# lab_1_arhipov_usb_i2c.net
KiCad netlist of a schematic drawn in Altium Designer
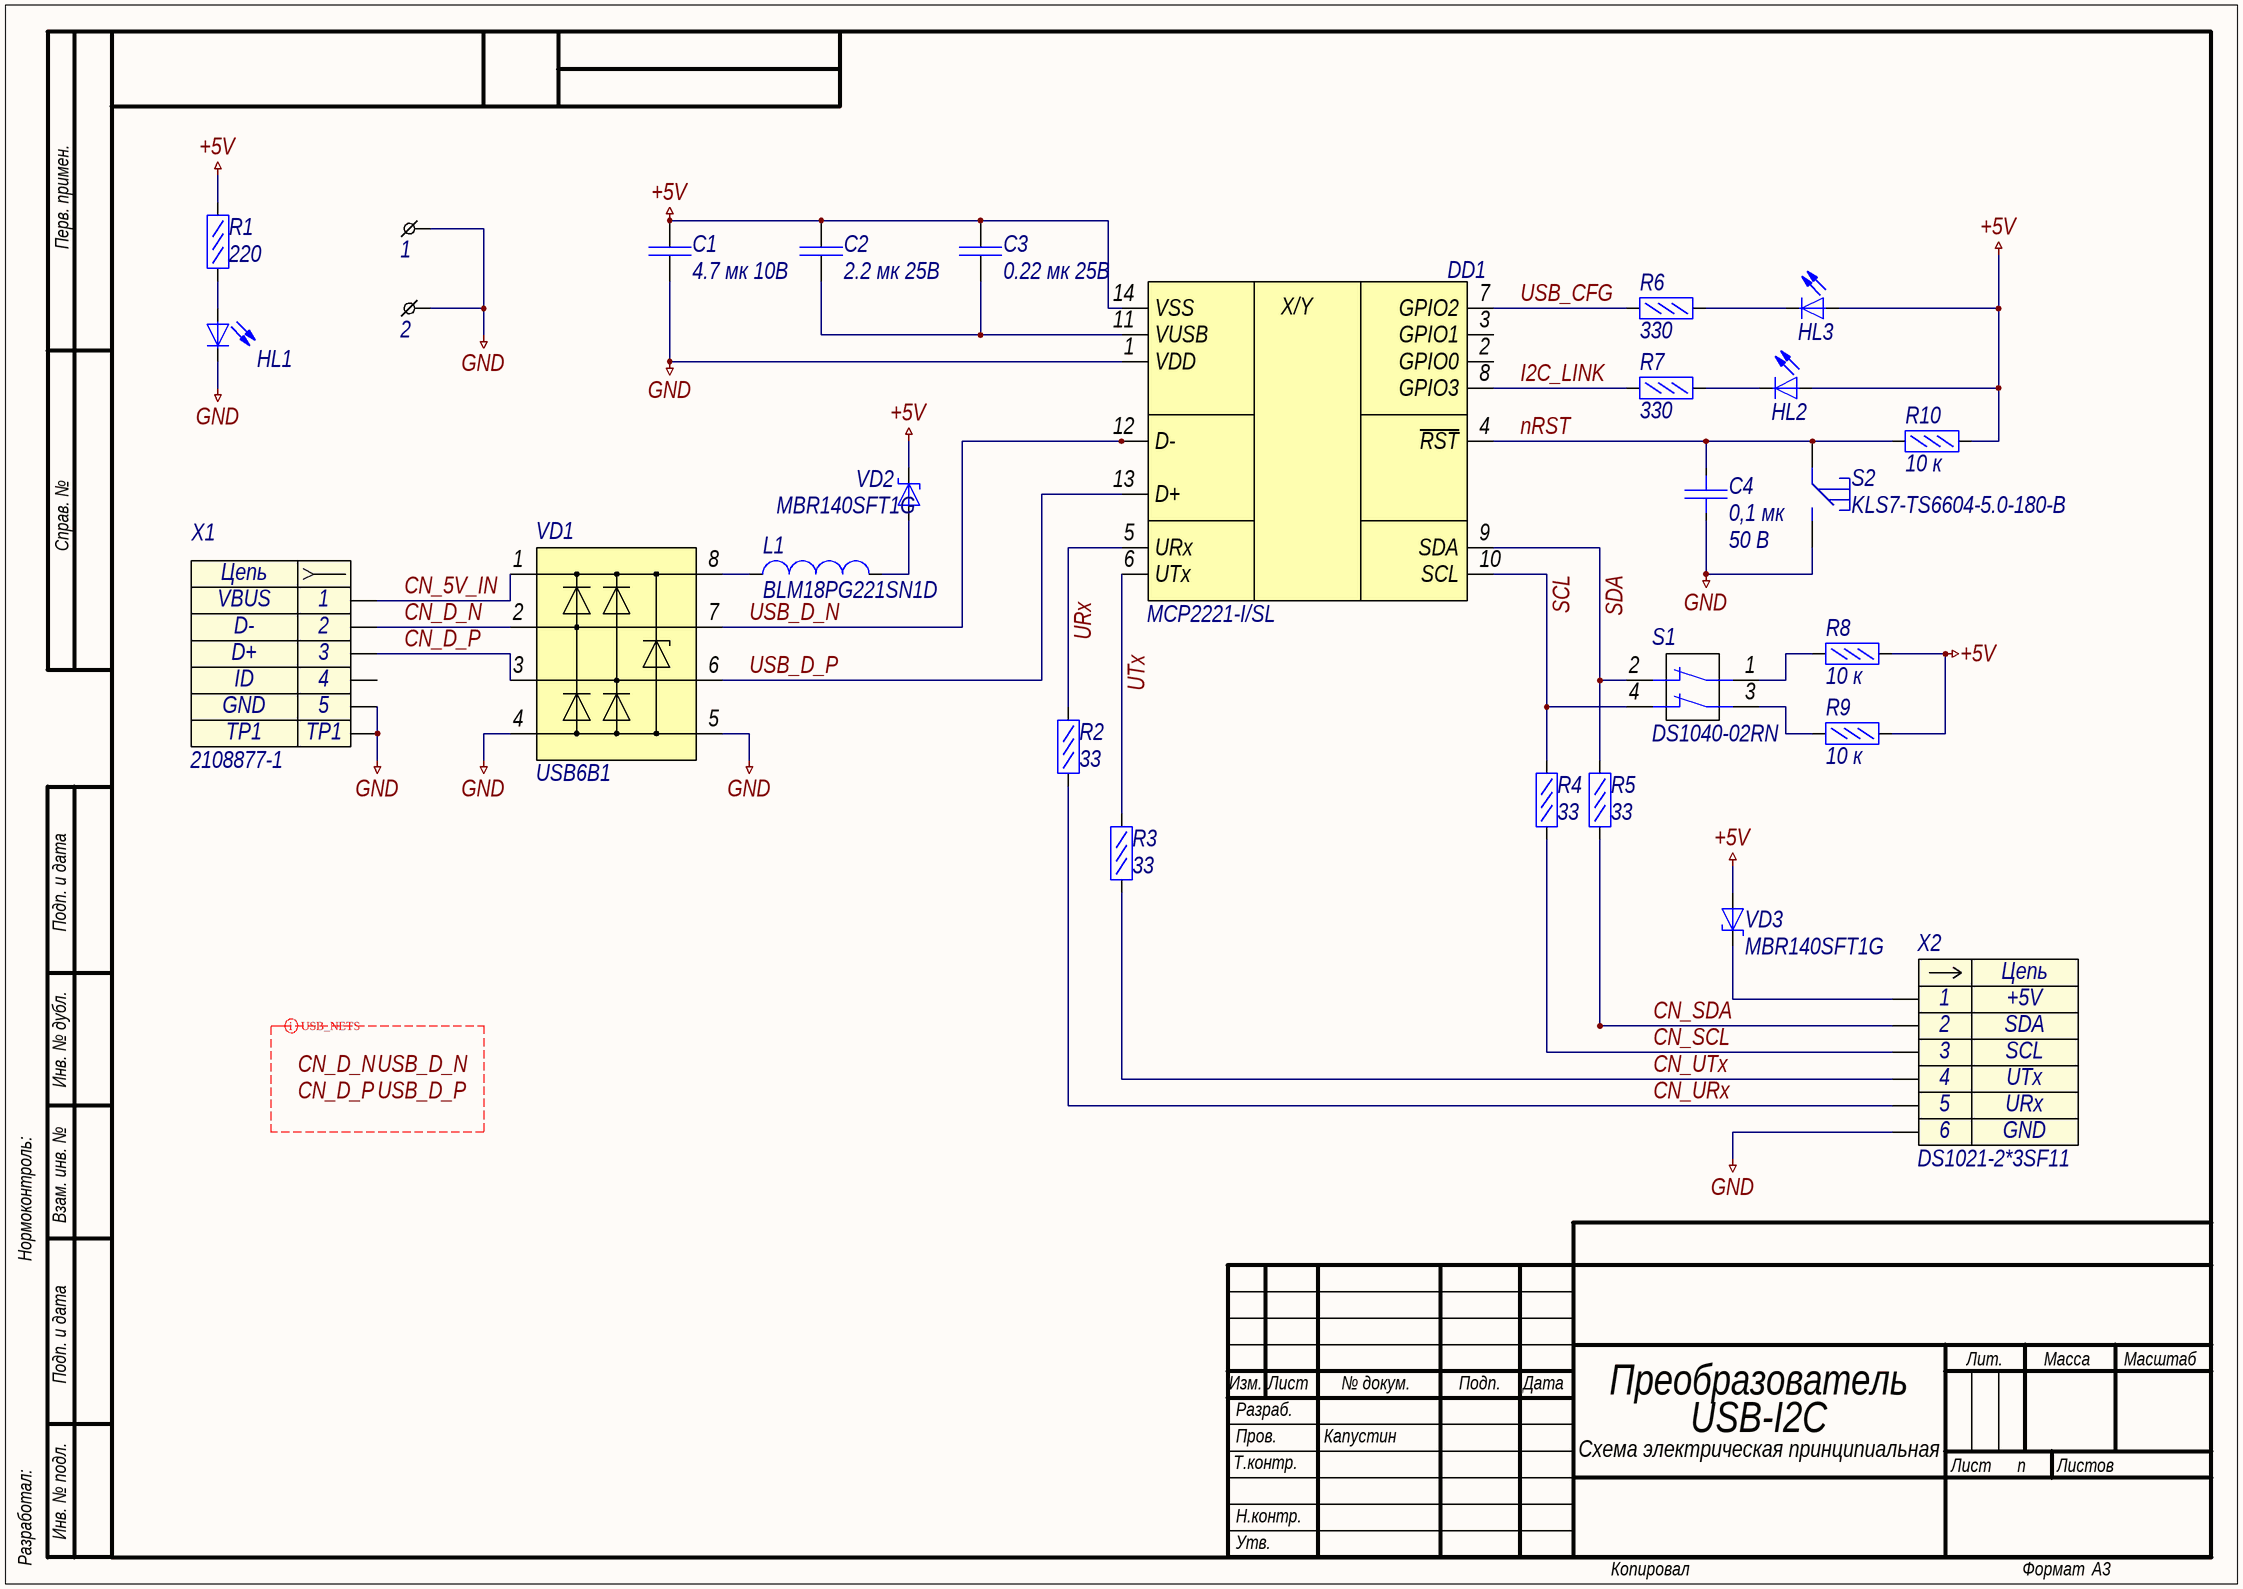
[diagram p0: lab_1_arhipov_usb_i2c.SchDoc]

(export (version "E")
  (design (tool "Eeschema 10.0.6"))
  (components
    (comp (ref "1")
      (value "MOUNTING_HOLE")
      (footprint "HOLE_1,6X3,3")
      (libsource (lib "Lib") (part "Отверстие 1,6x3,3"))
    )
    (comp (ref "2")
      (value "MOUNTING_HOLE")
      (footprint "HOLE_1,6X3,3")
      (libsource (lib "Lib") (part "Отверстие 1,6x3,3"))
    )
    (comp (ref "C1")
      (value "4.7 мк 10В")
      (footprint "c0805:C0805")
      (description "=Описание")
      (libsource (lib "Database_Students") (part "C-10.0V4.7mkF"))
    )
    (comp (ref "C2")
      (value "2.2 мк 25В")
      (footprint "c1206:C1206")
      (description "=Описание")
      (libsource (lib "Database_Students") (part "C-25.0V2.2mkF"))
    )
    (comp (ref "C3")
      (value "0.22 мк 25В")
      (footprint "smd2220")
      (description "=Описание")
      (libsource (lib "Database_Students") (part "C-25.0V0.22mkF"))
    )
    (comp (ref "C4")
      (value "0,1 мк")
      (footprint "C0603")
      (description "Конденсатор")
      (fields (field (name "НАПРЯЖЕНИЕ") "50 В"))
      (libsource (lib "Lib") (part "CL10B104KB8NNN"))
    )
    (comp (ref "DD1")
      (value "MCP2221-I/SL")
      (footprint "mcp2221:SOIC127P600X175-14N")
      (libsource (lib "mcp2221") (part "mcp2221"))
    )
    (comp (ref "HL1") (value "KP-1608SGC") (footprint "D0603") (libsource (lib "Lib") (part "KP-1608SGC")))
    (comp (ref "HL2") (value "KP-1608SGC") (footprint "D0603") (libsource (lib "Lib") (part "KP-1608SGC")))
    (comp (ref "HL3") (value "KP-1608SGC") (footprint "D0603") (libsource (lib "Lib") (part "KP-1608SGC")))
    (comp (ref "L1")
      (value "BLM18PG221SN1D")
      (footprint "L0603")
      (libsource (lib "Lib") (part "BLM18PG221SN1D"))
    )
    (comp (ref "R1")
      (value "220")
      (footprint "R0603")
      (description "Резистор 0,063Вт")
      (libsource (lib "Lib") (part "RC0603FR-07220RL"))
    )
    (comp (ref "R2")
      (value "33")
      (footprint "R0603")
      (description "Резистор 0,063Вт")
      (libsource (lib "Lib") (part "RC0603FR-0733RL"))
    )
    (comp (ref "R3")
      (value "33")
      (footprint "R0603")
      (description "Резистор 0,063Вт")
      (libsource (lib "Lib") (part "RC0603FR-0733RL"))
    )
    (comp (ref "R4")
      (value "33")
      (footprint "R0603")
      (description "Резистор 0,063Вт")
      (libsource (lib "Lib") (part "RC0603FR-0733RL"))
    )
    (comp (ref "R5")
      (value "33")
      (footprint "R0603")
      (description "Резистор 0,063Вт")
      (libsource (lib "Lib") (part "RC0603FR-0733RL"))
    )
    (comp (ref "R6")
      (value "330")
      (footprint "R0603")
      (description "Резистор 0,063Вт")
      (libsource (lib "Lib") (part "RC0603FR-07330RL"))
    )
    (comp (ref "R7")
      (value "330")
      (footprint "R0603")
      (description "Резистор 0,063Вт")
      (libsource (lib "Lib") (part "RC0603FR-07330RL"))
    )
    (comp (ref "R8")
      (value "10 к")
      (footprint "Lib:R0603")
      (description "Резистор 0,063Вт")
      (libsource (lib "Lib") (part "RC0603FR-0710KL"))
    )
    (comp (ref "R9")
      (value "10 к")
      (footprint "Lib:R0603")
      (description "Резистор 0,063Вт")
      (libsource (lib "Lib") (part "RC0603FR-0710KL"))
    )
    (comp (ref "R10")
      (value "10 к")
      (footprint "R0603")
      (description "Резистор 0,063Вт")
      (libsource (lib "Lib") (part "RC0603FR-0710KL"))
    )
    (comp (ref "S1")
      (value "DS1040-02RN")
      (footprint "Lib:DS1040-02RN")
      (libsource (lib "Lib") (part "DS1040-02RN_1"))
    )
    (comp (ref "S2")
      (value "KLS7-TS6604-5.0-180-B")
      (footprint "KLS7-TS6604_500")
      (libsource (lib "Lib") (part "KLS7-TS6604-5.0-180-B"))
    )
    (comp (ref "VD1") (value "USB6B1") (footprint "SO-8") (libsource (lib "Lib") (part "USB6B1")))
    (comp (ref "VD2")
      (value "MBR140SFT1G")
      (footprint "SOD-123FL_290X180X98")
      (libsource (lib "Lib") (part "MBR140SFT1G"))
    )
    (comp (ref "VD3")
      (value "MBR140SFT1G")
      (footprint "SOD-123FL_290X180X98")
      (libsource (lib "Lib") (part "MBR140SFT1G"))
    )
    (comp (ref "X1")
      (value "2108877-1")
      (footprint "2108877-1")
      (libsource (lib "2108877-1_micro_usb-b") (part "2108877-1_micro_usb-b"))
    )
    (comp (ref "X2")
      (value "DS1021-2*3SF11")
      (footprint "Lib:PLS-2,54-2X3-THT-V")
      (libsource (lib "Lib") (part "DS1021-2*3SF11"))
    )
  )
  (nets
    (net (code "1") (name "+5V") (class "Default")
      (node (ref "C1") (pin "2") (pinfunction "2_2") (pintype "passive"))
      (node (ref "C2") (pin "2") (pinfunction "2_2") (pintype "passive"))
      (node (ref "C3") (pin "2") (pinfunction "2_2") (pintype "passive"))
      (node (ref "DD1") (pin "14") (pinfunction "VSS_14") (pintype "passive"))
      (node (ref "HL2") (pin "1") (pinfunction "A_1") (pintype "passive"))
      (node (ref "HL3") (pin "1") (pinfunction "A_1") (pintype "passive"))
      (node (ref "R1") (pin "2") (pinfunction "2_2") (pintype "passive"))
      (node (ref "R10") (pin "2") (pinfunction "2_2") (pintype "passive"))
      (node (ref "R8") (pin "2") (pinfunction "2_2") (pintype "passive"))
      (node (ref "R9") (pin "2") (pinfunction "2_2") (pintype "passive"))
      (node (ref "VD2") (pin "2") (pinfunction "K_2") (pintype "passive"))
      (node (ref "VD3") (pin "1") (pinfunction "A_1") (pintype "passive"))
    )
    (net (code "2") (name "/CN_5V_IN") (class "Default")
      (node (ref "VD1") (pin "1") (pintype "passive"))
      (node (ref "X1") (pin "1") (pinfunction "1_1") (pintype "passive"))
    )
    (net (code "3") (name "/CN_D_N") (class "Default")
      (node (ref "VD1") (pin "2") (pintype "passive"))
      (node (ref "X1") (pin "2") (pinfunction "2_2") (pintype "passive"))
    )
    (net (code "4") (name "/CN_D_P") (class "Default")
      (node (ref "VD1") (pin "3") (pintype "passive"))
      (node (ref "X1") (pin "3") (pinfunction "3_3") (pintype "passive"))
    )
    (net (code "5") (name "/CN_SCL") (class "Default")
      (node (ref "R4") (pin "1") (pinfunction "1_1") (pintype "passive"))
      (node (ref "X2") (pin "3") (pinfunction "3_3") (pintype "passive"))
    )
    (net (code "6") (name "/CN_SDA") (class "Default")
      (node (ref "R5") (pin "1") (pinfunction "1_1") (pintype "passive"))
      (node (ref "X2") (pin "2") (pinfunction "2_2") (pintype "passive"))
    )
    (net (code "7") (name "/CN_URx") (class "Default")
      (node (ref "R2") (pin "1") (pinfunction "1_1") (pintype "passive"))
      (node (ref "X2") (pin "5") (pinfunction "5_5") (pintype "passive"))
    )
    (net (code "8") (name "/CN_UTx") (class "Default")
      (node (ref "R3") (pin "1") (pinfunction "1_1") (pintype "passive"))
      (node (ref "X2") (pin "4") (pinfunction "4_4") (pintype "passive"))
    )
    (net (code "9") (name "/I2C_LINK") (class "Default")
      (node (ref "DD1") (pin "8") (pinfunction "GPIO3_8") (pintype "passive"))
      (node (ref "R7") (pin "1") (pinfunction "1_1") (pintype "passive"))
    )
    (net (code "10") (name "/SCL") (class "Default")
      (node (ref "DD1") (pin "10") (pinfunction "SCL_10") (pintype "passive"))
      (node (ref "R4") (pin "2") (pinfunction "2_2") (pintype "passive"))
      (node (ref "S1") (pin "4") (pinfunction "4_4") (pintype "passive"))
    )
    (net (code "11") (name "/SDA") (class "Default")
      (node (ref "DD1") (pin "9") (pinfunction "SDA_9") (pintype "passive"))
      (node (ref "R5") (pin "2") (pinfunction "2_2") (pintype "passive"))
      (node (ref "S1") (pin "2") (pinfunction "2_2") (pintype "passive"))
    )
    (net (code "12") (name "/URx") (class "Default")
      (node (ref "DD1") (pin "5") (pinfunction "URx_5") (pintype "passive"))
      (node (ref "R2") (pin "2") (pinfunction "2_2") (pintype "passive"))
    )
    (net (code "13") (name "/USB_CFG") (class "Default")
      (node (ref "DD1") (pin "7") (pinfunction "GPIO2_7") (pintype "passive"))
      (node (ref "R6") (pin "1") (pinfunction "1_1") (pintype "passive"))
    )
    (net (code "14") (name "/USB_D_N") (class "Default")
      (node (ref "DD1") (pin "12") (pinfunction "D-_12") (pintype "passive"))
      (node (ref "VD1") (pin "7") (pintype "passive"))
    )
    (net (code "15") (name "/USB_D_P") (class "Default")
      (node (ref "DD1") (pin "13") (pinfunction "D+_13") (pintype "passive"))
      (node (ref "VD1") (pin "6") (pintype "passive"))
    )
    (net (code "16") (name "/UTx") (class "Default")
      (node (ref "DD1") (pin "6") (pinfunction "UTx_6") (pintype "passive"))
      (node (ref "R3") (pin "2") (pinfunction "2_2") (pintype "passive"))
    )
    (net (code "17") (name "/nRST") (class "Default")
      (node (ref "C4") (pin "2") (pinfunction "2_2") (pintype "passive"))
      (node (ref "DD1") (pin "4") (pinfunction "~{RST}_4") (pintype "passive"))
      (node (ref "R10") (pin "1") (pinfunction "1_1") (pintype "passive"))
      (node (ref "S2") (pin "1") (pinfunction "1_1") (pintype "passive"))
    )
    (net (code "18") (name "GND") (class "Default")
      (node (ref "1") (pin "1") (pinfunction "1_1") (pintype "passive"))
      (node (ref "2") (pin "1") (pinfunction "1_1") (pintype "passive"))
      (node (ref "C1") (pin "1") (pinfunction "1_1") (pintype "passive"))
      (node (ref "C4") (pin "1") (pinfunction "1_1") (pintype "passive"))
      (node (ref "DD1") (pin "1") (pinfunction "VDD_1") (pintype "passive"))
      (node (ref "HL1") (pin "2") (pinfunction "K_2") (pintype "passive"))
      (node (ref "S2") (pin "2") (pinfunction "2_2") (pintype "passive"))
      (node (ref "VD1") (pin "4") (pintype "passive"))
      (node (ref "VD1") (pin "5") (pintype "passive"))
      (node (ref "X1") (pin "5") (pinfunction "5_5") (pintype "passive"))
      (node (ref "X1") (pin "TP1") (pinfunction "TP1_TP1") (pintype "passive"))
      (node (ref "X2") (pin "6") (pinfunction "6_6") (pintype "passive"))
    )
    (net (code "19") (name "Net-(DD1-VUSB)") (class "Default")
      (node (ref "C2") (pin "1") (pinfunction "1_1") (pintype "passive"))
      (node (ref "C3") (pin "1") (pinfunction "1_1") (pintype "passive"))
      (node (ref "DD1") (pin "11") (pinfunction "VUSB_11") (pintype "passive"))
    )
    (net (code "20") (name "Net-(HL1-A)") (class "Default")
      (node (ref "HL1") (pin "1") (pinfunction "A_1") (pintype "passive"))
      (node (ref "R1") (pin "1") (pinfunction "1_1") (pintype "passive"))
    )
    (net (code "21") (name "Net-(HL2-K)") (class "Default")
      (node (ref "HL2") (pin "2") (pinfunction "K_2") (pintype "passive"))
      (node (ref "R7") (pin "2") (pinfunction "2_2") (pintype "passive"))
    )
    (net (code "22") (name "Net-(HL3-K)") (class "Default")
      (node (ref "HL3") (pin "2") (pinfunction "K_2") (pintype "passive"))
      (node (ref "R6") (pin "2") (pinfunction "2_2") (pintype "passive"))
    )
    (net (code "23") (name "Net-(L1-Pad1)") (class "Default")
      (node (ref "L1") (pin "1") (pinfunction "1_1") (pintype "passive"))
      (node (ref "VD1") (pin "8") (pintype "passive"))
    )
    (net (code "24") (name "Net-(R8-Pad1)") (class "Default")
      (node (ref "R8") (pin "1") (pinfunction "1_1") (pintype "passive"))
      (node (ref "S1") (pin "1") (pinfunction "1_1") (pintype "passive"))
    )
    (net (code "25") (name "Net-(R9-Pad1)") (class "Default")
      (node (ref "R9") (pin "1") (pinfunction "1_1") (pintype "passive"))
      (node (ref "S1") (pin "3") (pinfunction "3_3") (pintype "passive"))
    )
    (net (code "26") (name "Net-(VD2-A)") (class "Default")
      (node (ref "L1") (pin "2") (pinfunction "2_2") (pintype "passive"))
      (node (ref "VD2") (pin "1") (pinfunction "A_1") (pintype "passive"))
    )
    (net (code "27") (name "Net-(VD3-K)") (class "Default")
      (node (ref "VD3") (pin "2") (pinfunction "K_2") (pintype "passive"))
      (node (ref "X2") (pin "1") (pinfunction "1_1") (pintype "passive"))
    )
    (net (code "28") (name "unconnected-(DD1-GPIO0-Pad2)") (class "Default")
      (node (ref "DD1") (pin "2") (pinfunction "GPIO0_2") (pintype "passive"))
    )
    (net (code "29") (name "unconnected-(DD1-GPIO1-Pad3)") (class "Default")
      (node (ref "DD1") (pin "3") (pinfunction "GPIO1_3") (pintype "passive"))
    )
    (net (code "30") (name "unconnected-(X1-Pad4)") (class "Default")
      (node (ref "X1") (pin "4") (pinfunction "4_4") (pintype "passive"))
    )
  )
)
